# PUENTE_H.net
KiCad netlist of a schematic drawn in EAGLE
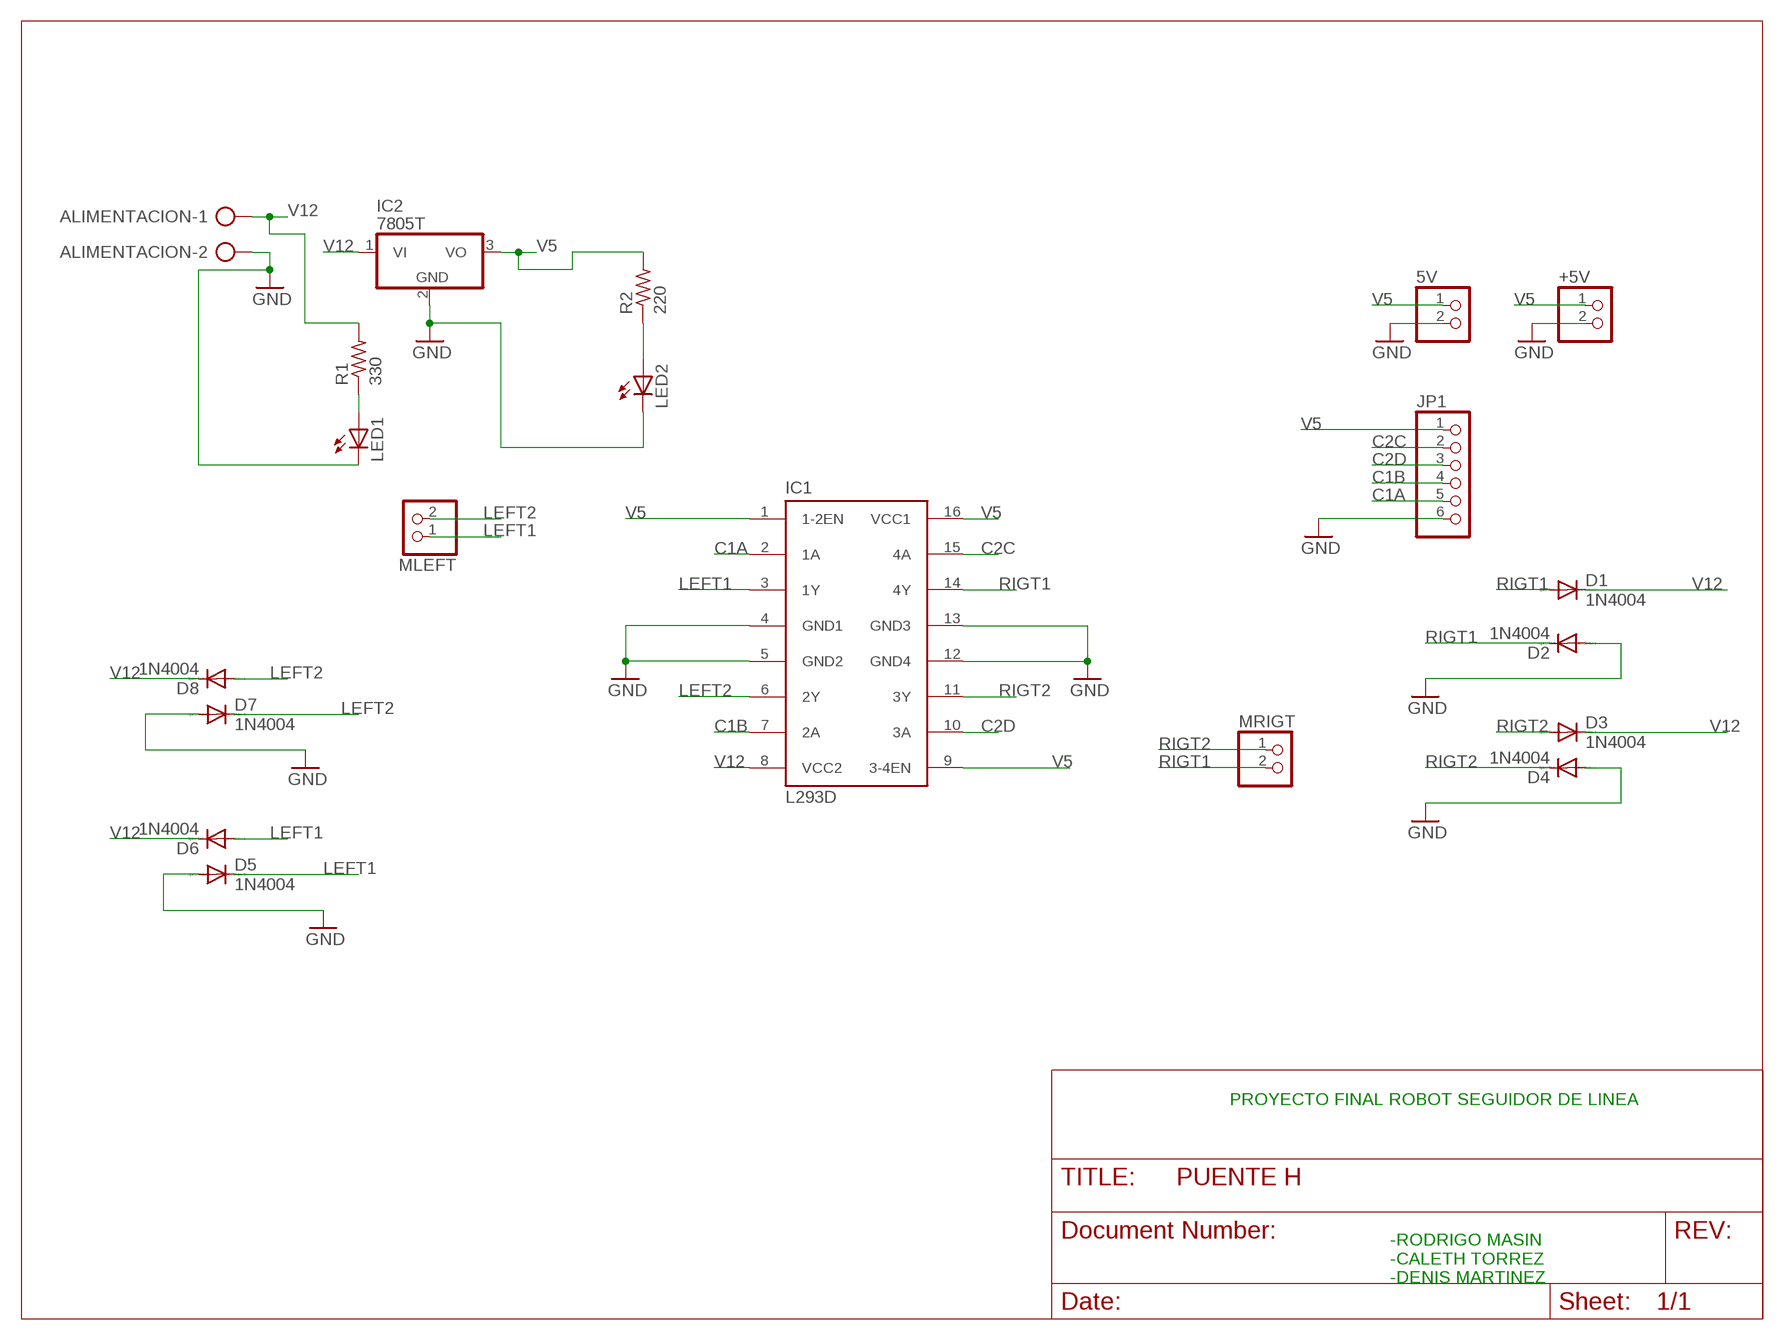
[diagram p0: schematic, sheet 1]

(export (version "E")
  (design (tool "Eeschema 10.0.6"))
  (components
    (comp (ref "+5V")
      (value "PINHD-1X2")
      (footprint "eagle-import:1X02")
      (libsource (lib "eagle-import") (part "PINHD-1X2"))
    )
    (comp (ref "5V")
      (value "PINHD-1X2")
      (footprint "eagle-import:1X02")
      (libsource (lib "eagle-import") (part "PINHD-1X2"))
    )
    (comp (ref "ALIMENTACION")
      (value "AK500/2-H")
      (footprint "eagle-import:AK500_2-H")
      (libsource (lib "eagle-import") (part "AK500/2-H"))
    )
    (comp (ref "D1")
      (value "1N4004")
      (footprint "eagle-import:DO41-10")
      (libsource (lib "eagle-import") (part "1N4004"))
    )
    (comp (ref "D2")
      (value "1N4004")
      (footprint "eagle-import:DO41-10")
      (libsource (lib "eagle-import") (part "1N4004"))
    )
    (comp (ref "D3")
      (value "1N4004")
      (footprint "eagle-import:DO41-10")
      (libsource (lib "eagle-import") (part "1N4004"))
    )
    (comp (ref "D4")
      (value "1N4004")
      (footprint "eagle-import:DO41-10")
      (libsource (lib "eagle-import") (part "1N4004"))
    )
    (comp (ref "D5")
      (value "1N4004")
      (footprint "eagle-import:DO41-10")
      (libsource (lib "eagle-import") (part "1N4004"))
    )
    (comp (ref "D6")
      (value "1N4004")
      (footprint "eagle-import:DO41-10")
      (libsource (lib "eagle-import") (part "1N4004"))
    )
    (comp (ref "D7")
      (value "1N4004")
      (footprint "eagle-import:DO41-10")
      (libsource (lib "eagle-import") (part "1N4004"))
    )
    (comp (ref "D8")
      (value "1N4004")
      (footprint "eagle-import:DO41-10")
      (libsource (lib "eagle-import") (part "1N4004"))
    )
    (comp (ref "IC1")
      (value "L293D")
      (footprint "eagle-import:DIL16")
      (libsource (lib "eagle-import") (part "L293D"))
    )
    (comp (ref "IC2")
      (value "7805T")
      (footprint "eagle-import:TO220H")
      (libsource (lib "eagle-import") (part "78T05"))
    )
    (comp (ref "JP1")
      (value "PINHD-1X6")
      (footprint "eagle-import:1X06")
      (libsource (lib "eagle-import") (part "PINHD-1X6"))
    )
    (comp (ref "LED1")
      (value "LED5MM")
      (footprint "eagle-import:LED5MM")
      (libsource (lib "eagle-import") (part "LED5MM"))
    )
    (comp (ref "LED2")
      (value "LED5MM")
      (footprint "eagle-import:LED5MM")
      (libsource (lib "eagle-import") (part "LED5MM"))
    )
    (comp (ref "MLEFT")
      (value "PINHD-1X2")
      (footprint "eagle-import:1X02")
      (libsource (lib "eagle-import") (part "PINHD-1X2"))
    )
    (comp (ref "MRIGT")
      (value "PINHD-1X2")
      (footprint "eagle-import:1X02")
      (libsource (lib "eagle-import") (part "PINHD-1X2"))
    )
    (comp (ref "R1")
      (value "330")
      (footprint "eagle-import:0204_7")
      (libsource (lib "eagle-import") (part "R-US_0204/7"))
    )
    (comp (ref "R2")
      (value "220")
      (footprint "eagle-import:0204_7")
      (libsource (lib "eagle-import") (part "R-US_0204/7"))
    )
  )
  (nets
    (net (code "1") (name "/C1A") (class "Default")
      (node (ref "IC1") (pin "2") (pinfunction "1A_2") (pintype "input"))
      (node (ref "JP1") (pin "5") (pinfunction "5_5") (pintype "passive"))
    )
    (net (code "2") (name "/C1B") (class "Default")
      (node (ref "IC1") (pin "7") (pinfunction "2A_7") (pintype "input"))
      (node (ref "JP1") (pin "4") (pinfunction "4_4") (pintype "passive"))
    )
    (net (code "3") (name "/C2C") (class "Default")
      (node (ref "IC1") (pin "15") (pinfunction "4A_15") (pintype "input"))
      (node (ref "JP1") (pin "2") (pinfunction "2_2") (pintype "passive"))
    )
    (net (code "4") (name "/C2D") (class "Default")
      (node (ref "IC1") (pin "10") (pinfunction "3A_10") (pintype "input"))
      (node (ref "JP1") (pin "3") (pinfunction "3_3") (pintype "passive"))
    )
    (net (code "5") (name "/LEFT1") (class "Default")
      (node (ref "D5") (pin "C") (pinfunction "C_C") (pintype "passive"))
      (node (ref "D6") (pin "A") (pinfunction "A_A") (pintype "passive"))
      (node (ref "IC1") (pin "3") (pinfunction "1Y_3") (pintype "output"))
      (node (ref "MLEFT") (pin "1") (pinfunction "1_1") (pintype "passive"))
    )
    (net (code "6") (name "/LEFT2") (class "Default")
      (node (ref "D7") (pin "C") (pinfunction "C_C") (pintype "passive"))
      (node (ref "D8") (pin "A") (pinfunction "A_A") (pintype "passive"))
      (node (ref "IC1") (pin "6") (pinfunction "2Y_6") (pintype "output"))
      (node (ref "MLEFT") (pin "2") (pinfunction "2_2") (pintype "passive"))
    )
    (net (code "7") (name "/RIGT1") (class "Default")
      (node (ref "D1") (pin "A") (pinfunction "A_A") (pintype "passive"))
      (node (ref "D2") (pin "C") (pinfunction "C_C") (pintype "passive"))
      (node (ref "IC1") (pin "14") (pinfunction "4Y_14") (pintype "output"))
      (node (ref "MRIGT") (pin "2") (pinfunction "2_2") (pintype "passive"))
    )
    (net (code "8") (name "/RIGT2") (class "Default")
      (node (ref "D3") (pin "A") (pinfunction "A_A") (pintype "passive"))
      (node (ref "D4") (pin "C") (pinfunction "C_C") (pintype "passive"))
      (node (ref "IC1") (pin "11") (pinfunction "3Y_11") (pintype "output"))
      (node (ref "MRIGT") (pin "1") (pinfunction "1_1") (pintype "passive"))
    )
    (net (code "9") (name "/V5") (class "Default")
      (node (ref "+5V") (pin "1") (pinfunction "1_1") (pintype "passive"))
      (node (ref "5V") (pin "1") (pinfunction "1_1") (pintype "passive"))
      (node (ref "IC1") (pin "1") (pinfunction "1-2EN_1") (pintype "input"))
      (node (ref "IC1") (pin "16") (pinfunction "VCC1_16") (pintype "power_in"))
      (node (ref "IC1") (pin "9") (pinfunction "3-4EN_9") (pintype "input"))
      (node (ref "IC2") (pin "3") (pinfunction "VO_3") (pintype "passive"))
      (node (ref "JP1") (pin "1") (pinfunction "1_1") (pintype "passive"))
      (node (ref "R2") (pin "2") (pinfunction "2_2") (pintype "passive"))
    )
    (net (code "10") (name "/V12") (class "Default")
      (node (ref "ALIMENTACION") (pin "1") (pinfunction "KL_1") (pintype "passive"))
      (node (ref "D1") (pin "C") (pinfunction "C_C") (pintype "passive"))
      (node (ref "D3") (pin "C") (pinfunction "C_C") (pintype "passive"))
      (node (ref "D6") (pin "C") (pinfunction "C_C") (pintype "passive"))
      (node (ref "D8") (pin "C") (pinfunction "C_C") (pintype "passive"))
      (node (ref "IC1") (pin "8") (pinfunction "VCC2_8") (pintype "power_in"))
      (node (ref "IC2") (pin "1") (pinfunction "VI_1") (pintype "input"))
      (node (ref "R1") (pin "2") (pinfunction "2_2") (pintype "passive"))
    )
    (net (code "11") (name "GND") (class "Default")
      (node (ref "+5V") (pin "2") (pinfunction "2_2") (pintype "passive"))
      (node (ref "5V") (pin "2") (pinfunction "2_2") (pintype "passive"))
      (node (ref "ALIMENTACION") (pin "2") (pinfunction "KL_2") (pintype "passive"))
      (node (ref "D2") (pin "A") (pinfunction "A_A") (pintype "passive"))
      (node (ref "D4") (pin "A") (pinfunction "A_A") (pintype "passive"))
      (node (ref "D5") (pin "A") (pinfunction "A_A") (pintype "passive"))
      (node (ref "D7") (pin "A") (pinfunction "A_A") (pintype "passive"))
      (node (ref "IC1") (pin "12") (pinfunction "GND4_12") (pintype "power_in"))
      (node (ref "IC1") (pin "13") (pinfunction "GND3_13") (pintype "power_in"))
      (node (ref "IC1") (pin "4") (pinfunction "GND1_4") (pintype "power_in"))
      (node (ref "IC1") (pin "5") (pinfunction "GND2_5") (pintype "power_in"))
      (node (ref "IC2") (pin "2") (pinfunction "GND_2") (pintype "passive"))
      (node (ref "JP1") (pin "6") (pinfunction "6_6") (pintype "passive"))
      (node (ref "LED1") (pin "K") (pinfunction "C_K") (pintype "passive"))
      (node (ref "LED2") (pin "K") (pinfunction "C_K") (pintype "passive"))
    )
    (net (code "12") (name "Net-(LED1-PadA)") (class "Default")
      (node (ref "LED1") (pin "A") (pinfunction "A_A") (pintype "passive"))
      (node (ref "R1") (pin "1") (pinfunction "1_1") (pintype "passive"))
    )
    (net (code "13") (name "Net-(LED2-PadA)") (class "Default")
      (node (ref "LED2") (pin "A") (pinfunction "A_A") (pintype "passive"))
      (node (ref "R2") (pin "1") (pinfunction "1_1") (pintype "passive"))
    )
  )
)
